# DASH_CAN.net
KiCad netlist of a schematic drawn in Altium Designer
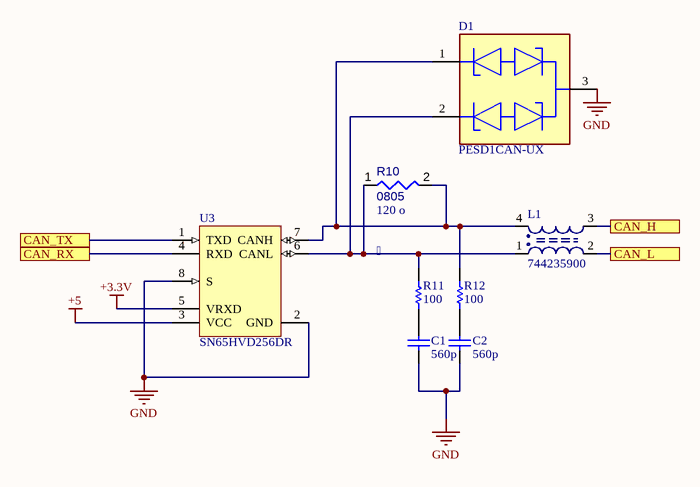
[diagram p0: DASH_CAN.SchDoc]

(export (version "E")
  (design (tool "Eeschema 10.0.6"))
  (components
    (comp (ref "C1")
      (value "560p")
      (footprint "CAPC1608X87X35NL15T15")
      (description ".1 uf")
      (fields (field (name "PART NUMBER") "C0603C104J3RAC7867") (field (name "MANUFACTURER") "Kemet"))
      (libsource (lib "Altium Content Vault") (part "CAP"))
    )
    (comp (ref "C2")
      (value "560p")
      (footprint "CAPC1608X87X35NL15T15")
      (description ".1 uf")
      (fields (field (name "PART NUMBER") "C0603C104J3RAC7867") (field (name "MANUFACTURER") "Kemet"))
      (libsource (lib "Altium Content Vault") (part "CAP"))
    )
    (comp (ref "D1")
      (value "PESD1CAN-UX")
      (footprint "FP-SOT323-MFG")
      (description "TVS DIODE 24V 50V SC70-3")
      (libsource (lib "Altium Content Vault") (part "04d57993b6b7b0f5b3c95ba4f97dea0"))
    )
    (comp (ref "L1")
      (value "744235900")
      (footprint "WE-CNSW 1812")
      (description "SMD Shielded Coupled Inductor WE-CNSW, Z=90 Ohm")
      (fields (field (name "MANUFACTURER") "Wuerth Elektronik"))
      (libsource (lib "Altium Content Vault") (part "WE-IND-INDUCTOR-4Q"))
    )
    (comp (ref "R10")
      (value "0805")
      (footprint "RESC0805(2012)_L")
      (description "Chip Resistor, 4,7 Ohms, +/-5 %, 125 mW, -55 to 155 degC, 0805")
      (fields
        (field (name "ALTIUM_VALUE") "120 o")
        (field (name "MAX OPERATING TEMPERATURE") "")
        (field (name "AVAILABLE PREVIEW IMAGES") "2D")
      )
      (libsource (lib "") (part "Symbol_1"))
    )
    (comp (ref "R11")
      (value "100")
      (footprint "RESC1608X55X25ML10T15")
      (description "Chip Resistor, 0 Ohm, 0.1 W, -55 to 155 degC, 0603 (1608 Metric)")
      (libsource (lib "Illini Formula Electric") (part "Symbol"))
    )
    (comp (ref "R12")
      (value "100")
      (footprint "RESC1608X55X25ML10T15")
      (description "Chip Resistor, 0 Ohm, 0.1 W, -55 to 155 degC, 0603 (1608 Metric)")
      (libsource (lib "Illini Formula Electric") (part "Symbol"))
    )
    (comp (ref "U3")
      (value "SN65HVD256DR")
      (footprint "D0008A_L")
      (fields (field (name "MANUFACTURER") "Texas Instruments"))
      (libsource (lib "Altium Content Vault") (part "TI-SN65HVD256-SOIC_D-8"))
    )
  )
  (nets
    (net (code "1") (name "+3.3V") (class "Default")
      (node (ref "U3") (pin "5") (pinfunction "VRXD_5") (pintype "power_in"))
    )
    (net (code "2") (name "+5") (class "Default")
      (node (ref "U3") (pin "3") (pinfunction "VCC_3") (pintype "power_in"))
    )
    (net (code "3") (name "/CAN_H") (class "Default")
      (node (ref "L1") (pin "3") (pinfunction "3_3") (pintype "passive"))
    )
    (net (code "4") (name "/CAN_L") (class "Default")
      (node (ref "L1") (pin "2") (pinfunction "2_2") (pintype "passive"))
    )
    (net (code "5") (name "/CAN_RX") (class "Default")
      (node (ref "U3") (pin "4") (pinfunction "RXD_4") (pintype "tri_state"))
    )
    (net (code "6") (name "/CAN_TX") (class "Default")
      (node (ref "U3") (pin "1") (pinfunction "TXD_1") (pintype "input"))
    )
    (net (code "7") (name "GND") (class "Default")
      (node (ref "C1") (pin "1") (pinfunction "1_1") (pintype "passive"))
      (node (ref "C2") (pin "1") (pinfunction "1_1") (pintype "passive"))
      (node (ref "D1") (pin "3") (pinfunction "common_cathode_3") (pintype "passive"))
      (node (ref "U3") (pin "2") (pinfunction "GND_2") (pintype "power_in"))
      (node (ref "U3") (pin "8") (pinfunction "S_8") (pintype "input"))
    )
    (net (code "8") (name "Net-(C1-Pad2)") (class "Default")
      (node (ref "C1") (pin "2") (pinfunction "2_2") (pintype "passive"))
      (node (ref "R11") (pin "1") (pinfunction "1_1") (pintype "passive"))
    )
    (net (code "9") (name "Net-(C2-Pad2)") (class "Default")
      (node (ref "C2") (pin "2") (pinfunction "2_2") (pintype "passive"))
      (node (ref "R12") (pin "1") (pinfunction "1_1") (pintype "passive"))
    )
    (net (code "10") (name "Net-(D1-cathode_1)") (class "Default")
      (node (ref "D1") (pin "1") (pinfunction "cathode_1_1") (pintype "passive"))
      (node (ref "L1") (pin "4") (pinfunction "4_4") (pintype "passive"))
      (node (ref "R10") (pin "2") (pinfunction "2_2") (pintype "passive"))
      (node (ref "R12") (pin "2") (pinfunction "2_2") (pintype "passive"))
      (node (ref "U3") (pin "7") (pinfunction "CANH_7") (pintype "bidirectional"))
    )
    (net (code "11") (name "Net-(D1-cathode_2)") (class "Default")
      (node (ref "D1") (pin "2") (pinfunction "cathode_2_2") (pintype "passive"))
      (node (ref "L1") (pin "1") (pinfunction "1_1") (pintype "passive"))
      (node (ref "R10") (pin "1") (pinfunction "1_1") (pintype "passive"))
      (node (ref "R11") (pin "2") (pinfunction "2_2") (pintype "passive"))
      (node (ref "U3") (pin "6") (pinfunction "CANL_6") (pintype "bidirectional"))
    )
  )
)
